# relays1.net
KiCad netlist of a schematic drawn in Altium Designer
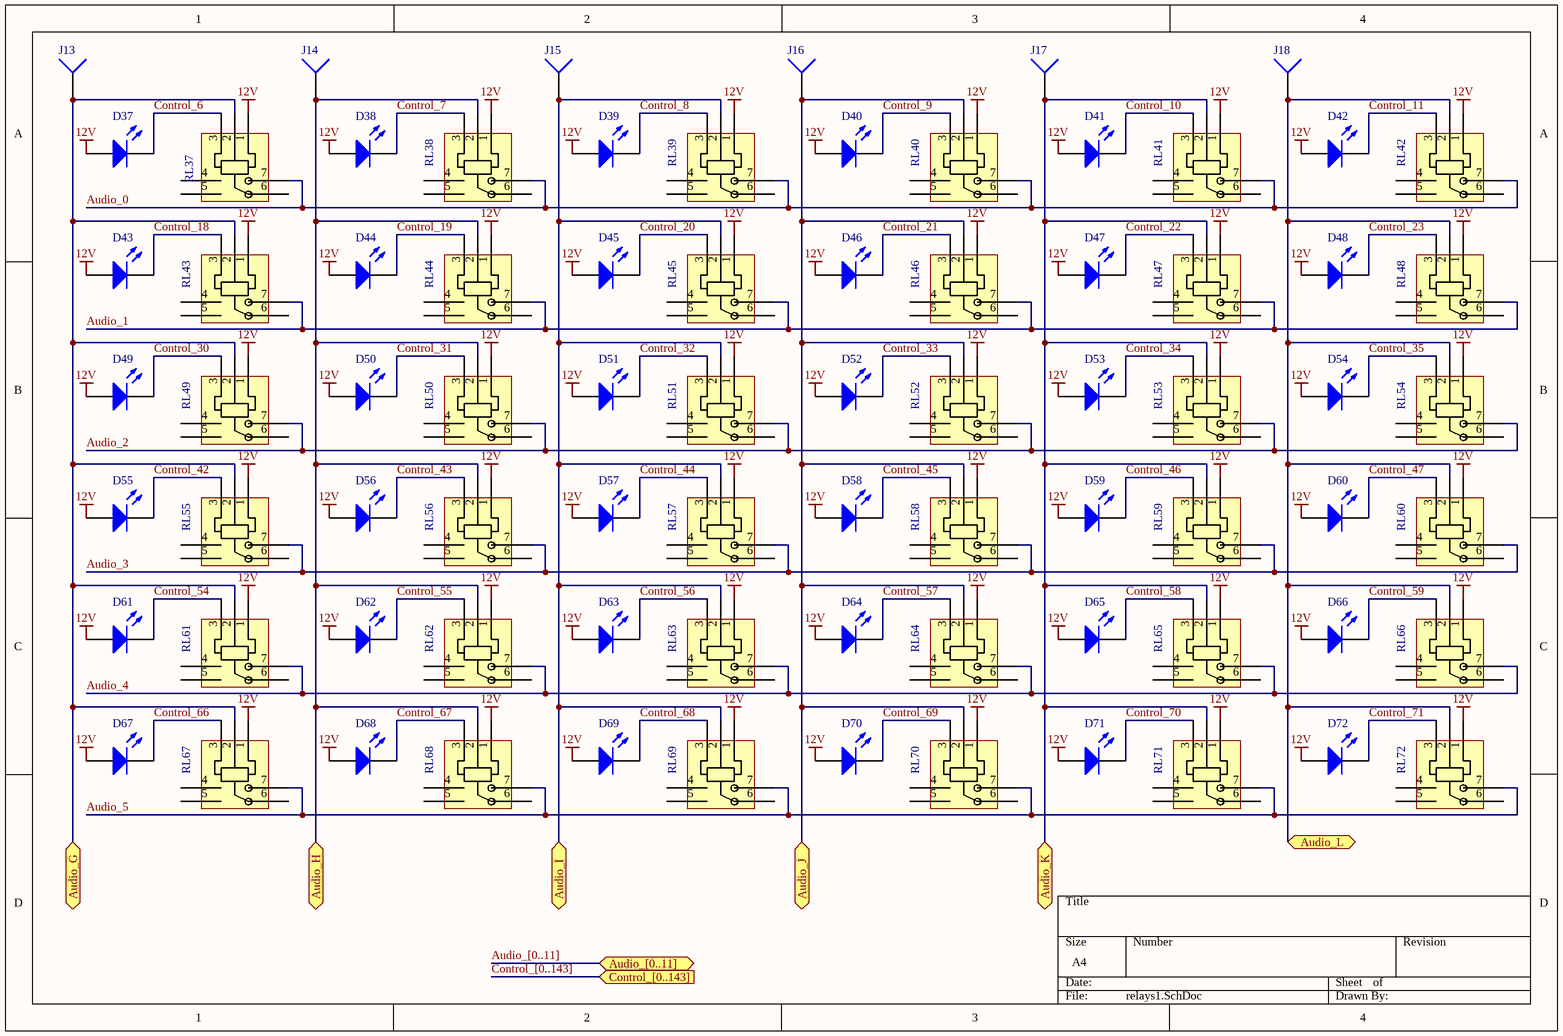
[diagram p0: relays1.SchDoc]

(export (version "E")
  (design (tool "Eeschema 10.0.6"))
  (components
    (comp (ref "D37")
      (value "LED0")
      (footprint "LED_round_5mm")
      (description "Typical INFRARED GaAs LED")
      (fields (field (name "PUBLISHER") "Altium Limited"))
      (libsource (lib "Miscellaneous Devices") (part "LED0"))
    )
    (comp (ref "D38")
      (value "LED0")
      (footprint "LED_round_5mm")
      (description "Typical INFRARED GaAs LED")
      (fields (field (name "PUBLISHER") "Altium Limited"))
      (libsource (lib "Miscellaneous Devices") (part "LED0"))
    )
    (comp (ref "D39")
      (value "LED0")
      (footprint "LED_round_5mm")
      (description "Typical INFRARED GaAs LED")
      (fields (field (name "PUBLISHER") "Altium Limited"))
      (libsource (lib "Miscellaneous Devices") (part "LED0"))
    )
    (comp (ref "D40")
      (value "LED0")
      (footprint "LED_round_5mm")
      (description "Typical INFRARED GaAs LED")
      (fields (field (name "PUBLISHER") "Altium Limited"))
      (libsource (lib "Miscellaneous Devices") (part "LED0"))
    )
    (comp (ref "D41")
      (value "LED0")
      (footprint "LED_round_5mm")
      (description "Typical INFRARED GaAs LED")
      (fields (field (name "PUBLISHER") "Altium Limited"))
      (libsource (lib "Miscellaneous Devices") (part "LED0"))
    )
    (comp (ref "D42")
      (value "LED0")
      (footprint "LED_round_5mm")
      (description "Typical INFRARED GaAs LED")
      (fields (field (name "PUBLISHER") "Altium Limited"))
      (libsource (lib "Miscellaneous Devices") (part "LED0"))
    )
    (comp (ref "D43")
      (value "LED0")
      (footprint "LED_round_5mm")
      (description "Typical INFRARED GaAs LED")
      (fields (field (name "PUBLISHER") "Altium Limited"))
      (libsource (lib "Miscellaneous Devices") (part "LED0"))
    )
    (comp (ref "D44")
      (value "LED0")
      (footprint "LED_round_5mm")
      (description "Typical INFRARED GaAs LED")
      (fields (field (name "PUBLISHER") "Altium Limited"))
      (libsource (lib "Miscellaneous Devices") (part "LED0"))
    )
    (comp (ref "D45")
      (value "LED0")
      (footprint "LED_round_5mm")
      (description "Typical INFRARED GaAs LED")
      (fields (field (name "PUBLISHER") "Altium Limited"))
      (libsource (lib "Miscellaneous Devices") (part "LED0"))
    )
    (comp (ref "D46")
      (value "LED0")
      (footprint "LED_round_5mm")
      (description "Typical INFRARED GaAs LED")
      (fields (field (name "PUBLISHER") "Altium Limited"))
      (libsource (lib "Miscellaneous Devices") (part "LED0"))
    )
    (comp (ref "D47")
      (value "LED0")
      (footprint "LED_round_5mm")
      (description "Typical INFRARED GaAs LED")
      (fields (field (name "PUBLISHER") "Altium Limited"))
      (libsource (lib "Miscellaneous Devices") (part "LED0"))
    )
    (comp (ref "D48")
      (value "LED0")
      (footprint "LED_round_5mm")
      (description "Typical INFRARED GaAs LED")
      (fields (field (name "PUBLISHER") "Altium Limited"))
      (libsource (lib "Miscellaneous Devices") (part "LED0"))
    )
    (comp (ref "D49")
      (value "LED0")
      (footprint "LED_round_5mm")
      (description "Typical INFRARED GaAs LED")
      (fields (field (name "PUBLISHER") "Altium Limited"))
      (libsource (lib "Miscellaneous Devices") (part "LED0"))
    )
    (comp (ref "D50")
      (value "LED0")
      (footprint "LED_round_5mm")
      (description "Typical INFRARED GaAs LED")
      (fields (field (name "PUBLISHER") "Altium Limited"))
      (libsource (lib "Miscellaneous Devices") (part "LED0"))
    )
    (comp (ref "D51")
      (value "LED0")
      (footprint "LED_round_5mm")
      (description "Typical INFRARED GaAs LED")
      (fields (field (name "PUBLISHER") "Altium Limited"))
      (libsource (lib "Miscellaneous Devices") (part "LED0"))
    )
    (comp (ref "D52")
      (value "LED0")
      (footprint "LED_round_5mm")
      (description "Typical INFRARED GaAs LED")
      (fields (field (name "PUBLISHER") "Altium Limited"))
      (libsource (lib "Miscellaneous Devices") (part "LED0"))
    )
    (comp (ref "D53")
      (value "LED0")
      (footprint "LED_round_5mm")
      (description "Typical INFRARED GaAs LED")
      (fields (field (name "PUBLISHER") "Altium Limited"))
      (libsource (lib "Miscellaneous Devices") (part "LED0"))
    )
    (comp (ref "D54")
      (value "LED0")
      (footprint "LED_round_5mm")
      (description "Typical INFRARED GaAs LED")
      (fields (field (name "PUBLISHER") "Altium Limited"))
      (libsource (lib "Miscellaneous Devices") (part "LED0"))
    )
    (comp (ref "D55")
      (value "LED0")
      (footprint "LED_round_5mm")
      (description "Typical INFRARED GaAs LED")
      (fields (field (name "PUBLISHER") "Altium Limited"))
      (libsource (lib "Miscellaneous Devices") (part "LED0"))
    )
    (comp (ref "D56")
      (value "LED0")
      (footprint "LED_round_5mm")
      (description "Typical INFRARED GaAs LED")
      (fields (field (name "PUBLISHER") "Altium Limited"))
      (libsource (lib "Miscellaneous Devices") (part "LED0"))
    )
    (comp (ref "D57")
      (value "LED0")
      (footprint "LED_round_5mm")
      (description "Typical INFRARED GaAs LED")
      (fields (field (name "PUBLISHER") "Altium Limited"))
      (libsource (lib "Miscellaneous Devices") (part "LED0"))
    )
    (comp (ref "D58")
      (value "LED0")
      (footprint "LED_round_5mm")
      (description "Typical INFRARED GaAs LED")
      (fields (field (name "PUBLISHER") "Altium Limited"))
      (libsource (lib "Miscellaneous Devices") (part "LED0"))
    )
    (comp (ref "D59")
      (value "LED0")
      (footprint "LED_round_5mm")
      (description "Typical INFRARED GaAs LED")
      (fields (field (name "PUBLISHER") "Altium Limited"))
      (libsource (lib "Miscellaneous Devices") (part "LED0"))
    )
    (comp (ref "D60")
      (value "LED0")
      (footprint "LED_round_5mm")
      (description "Typical INFRARED GaAs LED")
      (fields (field (name "PUBLISHER") "Altium Limited"))
      (libsource (lib "Miscellaneous Devices") (part "LED0"))
    )
    (comp (ref "D61")
      (value "LED0")
      (footprint "LED_round_5mm")
      (description "Typical INFRARED GaAs LED")
      (fields (field (name "PUBLISHER") "Altium Limited"))
      (libsource (lib "Miscellaneous Devices") (part "LED0"))
    )
    (comp (ref "D62")
      (value "LED0")
      (footprint "LED_round_5mm")
      (description "Typical INFRARED GaAs LED")
      (fields (field (name "PUBLISHER") "Altium Limited"))
      (libsource (lib "Miscellaneous Devices") (part "LED0"))
    )
    (comp (ref "D63")
      (value "LED0")
      (footprint "LED_round_5mm")
      (description "Typical INFRARED GaAs LED")
      (fields (field (name "PUBLISHER") "Altium Limited"))
      (libsource (lib "Miscellaneous Devices") (part "LED0"))
    )
    (comp (ref "D64")
      (value "LED0")
      (footprint "LED_round_5mm")
      (description "Typical INFRARED GaAs LED")
      (fields (field (name "PUBLISHER") "Altium Limited"))
      (libsource (lib "Miscellaneous Devices") (part "LED0"))
    )
    (comp (ref "D65")
      (value "LED0")
      (footprint "LED_round_5mm")
      (description "Typical INFRARED GaAs LED")
      (fields (field (name "PUBLISHER") "Altium Limited"))
      (libsource (lib "Miscellaneous Devices") (part "LED0"))
    )
    (comp (ref "D66")
      (value "LED0")
      (footprint "LED_round_5mm")
      (description "Typical INFRARED GaAs LED")
      (fields (field (name "PUBLISHER") "Altium Limited"))
      (libsource (lib "Miscellaneous Devices") (part "LED0"))
    )
    (comp (ref "D67")
      (value "LED0")
      (footprint "LED_round_5mm")
      (description "Typical INFRARED GaAs LED")
      (fields (field (name "PUBLISHER") "Altium Limited"))
      (libsource (lib "Miscellaneous Devices") (part "LED0"))
    )
    (comp (ref "D68")
      (value "LED0")
      (footprint "LED_round_5mm")
      (description "Typical INFRARED GaAs LED")
      (fields (field (name "PUBLISHER") "Altium Limited"))
      (libsource (lib "Miscellaneous Devices") (part "LED0"))
    )
    (comp (ref "D69")
      (value "LED0")
      (footprint "LED_round_5mm")
      (description "Typical INFRARED GaAs LED")
      (fields (field (name "PUBLISHER") "Altium Limited"))
      (libsource (lib "Miscellaneous Devices") (part "LED0"))
    )
    (comp (ref "D70")
      (value "LED0")
      (footprint "LED_round_5mm")
      (description "Typical INFRARED GaAs LED")
      (fields (field (name "PUBLISHER") "Altium Limited"))
      (libsource (lib "Miscellaneous Devices") (part "LED0"))
    )
    (comp (ref "D71")
      (value "LED0")
      (footprint "LED_round_5mm")
      (description "Typical INFRARED GaAs LED")
      (fields (field (name "PUBLISHER") "Altium Limited"))
      (libsource (lib "Miscellaneous Devices") (part "LED0"))
    )
    (comp (ref "D72")
      (value "LED0")
      (footprint "LED_round_5mm")
      (description "Typical INFRARED GaAs LED")
      (fields (field (name "PUBLISHER") "Altium Limited"))
      (libsource (lib "Miscellaneous Devices") (part "LED0"))
    )
    (comp (ref "J13")
      (value "Audio")
      (footprint "Conn_1_2x4")
      (description "Socket")
      (fields (field (name "PUBLISHER") "Altium Limited"))
      (libsource (lib "Miscellaneous Connectors") (part "Socket"))
    )
    (comp (ref "J14")
      (value "Audio")
      (footprint "Conn_1_2x4")
      (description "Socket")
      (fields (field (name "PUBLISHER") "Altium Limited"))
      (libsource (lib "Miscellaneous Connectors") (part "Socket"))
    )
    (comp (ref "J15")
      (value "Audio")
      (footprint "Conn_1_2x4")
      (description "Socket")
      (fields (field (name "PUBLISHER") "Altium Limited"))
      (libsource (lib "Miscellaneous Connectors") (part "Socket"))
    )
    (comp (ref "J16")
      (value "Audio")
      (footprint "Conn_1_2x4")
      (description "Socket")
      (fields (field (name "PUBLISHER") "Altium Limited"))
      (libsource (lib "Miscellaneous Connectors") (part "Socket"))
    )
    (comp (ref "J17")
      (value "Audio")
      (footprint "Conn_1_2x4")
      (description "Socket")
      (fields (field (name "PUBLISHER") "Altium Limited"))
      (libsource (lib "Miscellaneous Connectors") (part "Socket"))
    )
    (comp (ref "J18")
      (value "Audio")
      (footprint "Conn_1_2x4")
      (description "Socket")
      (fields (field (name "PUBLISHER") "Altium Limited"))
      (libsource (lib "Miscellaneous Connectors") (part "Socket"))
    )
    (comp (ref "RL37")
      (value "Relay")
      (footprint "Relay_FRA3")
      (description "Miniature power relay")
      (fields (field (name "PART NUMBER") "FRA3C-DC12"))
      (libsource (lib "tech-thing") (part "Relay_FRA3"))
    )
    (comp (ref "RL38")
      (value "Relay")
      (footprint "Relay_FRA3")
      (description "Miniature power relay")
      (fields (field (name "PART NUMBER") "FRA3C-DC12"))
      (libsource (lib "tech-thing") (part "Relay_FRA3"))
    )
    (comp (ref "RL39")
      (value "Relay")
      (footprint "Relay_FRA3")
      (description "Miniature power relay")
      (fields (field (name "PART NUMBER") "FRA3C-DC12"))
      (libsource (lib "tech-thing") (part "Relay_FRA3"))
    )
    (comp (ref "RL40")
      (value "Relay")
      (footprint "Relay_FRA3")
      (description "Miniature power relay")
      (fields (field (name "PART NUMBER") "FRA3C-DC12"))
      (libsource (lib "tech-thing") (part "Relay_FRA3"))
    )
    (comp (ref "RL41")
      (value "Relay")
      (footprint "Relay_FRA3")
      (description "Miniature power relay")
      (fields (field (name "PART NUMBER") "FRA3C-DC12"))
      (libsource (lib "tech-thing") (part "Relay_FRA3"))
    )
    (comp (ref "RL42")
      (value "Relay")
      (footprint "Relay_FRA3")
      (description "Miniature power relay")
      (fields (field (name "PART NUMBER") "FRA3C-DC12"))
      (libsource (lib "tech-thing") (part "Relay_FRA3"))
    )
    (comp (ref "RL43")
      (value "Relay")
      (footprint "Relay_FRA3")
      (description "Miniature power relay")
      (fields (field (name "PART NUMBER") "FRA3C-DC12"))
      (libsource (lib "tech-thing") (part "Relay_FRA3"))
    )
    (comp (ref "RL44")
      (value "Relay")
      (footprint "Relay_FRA3")
      (description "Miniature power relay")
      (fields (field (name "PART NUMBER") "FRA3C-DC12"))
      (libsource (lib "tech-thing") (part "Relay_FRA3"))
    )
    (comp (ref "RL45")
      (value "Relay")
      (footprint "Relay_FRA3")
      (description "Miniature power relay")
      (fields (field (name "PART NUMBER") "FRA3C-DC12"))
      (libsource (lib "tech-thing") (part "Relay_FRA3"))
    )
    (comp (ref "RL46")
      (value "Relay")
      (footprint "Relay_FRA3")
      (description "Miniature power relay")
      (fields (field (name "PART NUMBER") "FRA3C-DC12"))
      (libsource (lib "tech-thing") (part "Relay_FRA3"))
    )
    (comp (ref "RL47")
      (value "Relay")
      (footprint "Relay_FRA3")
      (description "Miniature power relay")
      (fields (field (name "PART NUMBER") "FRA3C-DC12"))
      (libsource (lib "tech-thing") (part "Relay_FRA3"))
    )
    (comp (ref "RL48")
      (value "Relay")
      (footprint "Relay_FRA3")
      (description "Miniature power relay")
      (fields (field (name "PART NUMBER") "FRA3C-DC12"))
      (libsource (lib "tech-thing") (part "Relay_FRA3"))
    )
    (comp (ref "RL49")
      (value "Relay")
      (footprint "Relay_FRA3")
      (description "Miniature power relay")
      (fields (field (name "PART NUMBER") "FRA3C-DC12"))
      (libsource (lib "tech-thing") (part "Relay_FRA3"))
    )
    (comp (ref "RL50")
      (value "Relay")
      (footprint "Relay_FRA3")
      (description "Miniature power relay")
      (fields (field (name "PART NUMBER") "FRA3C-DC12"))
      (libsource (lib "tech-thing") (part "Relay_FRA3"))
    )
    (comp (ref "RL51")
      (value "Relay")
      (footprint "Relay_FRA3")
      (description "Miniature power relay")
      (fields (field (name "PART NUMBER") "FRA3C-DC12"))
      (libsource (lib "tech-thing") (part "Relay_FRA3"))
    )
    (comp (ref "RL52")
      (value "Relay")
      (footprint "Relay_FRA3")
      (description "Miniature power relay")
      (fields (field (name "PART NUMBER") "FRA3C-DC12"))
      (libsource (lib "tech-thing") (part "Relay_FRA3"))
    )
    (comp (ref "RL53")
      (value "Relay")
      (footprint "Relay_FRA3")
      (description "Miniature power relay")
      (fields (field (name "PART NUMBER") "FRA3C-DC12"))
      (libsource (lib "tech-thing") (part "Relay_FRA3"))
    )
    (comp (ref "RL54")
      (value "Relay")
      (footprint "Relay_FRA3")
      (description "Miniature power relay")
      (fields (field (name "PART NUMBER") "FRA3C-DC12"))
      (libsource (lib "tech-thing") (part "Relay_FRA3"))
    )
    (comp (ref "RL55")
      (value "Relay")
      (footprint "Relay_FRA3")
      (description "Miniature power relay")
      (fields (field (name "PART NUMBER") "FRA3C-DC12"))
      (libsource (lib "tech-thing") (part "Relay_FRA3"))
    )
    (comp (ref "RL56")
      (value "Relay")
      (footprint "Relay_FRA3")
      (description "Miniature power relay")
      (fields (field (name "PART NUMBER") "FRA3C-DC12"))
      (libsource (lib "tech-thing") (part "Relay_FRA3"))
    )
    (comp (ref "RL57")
      (value "Relay")
      (footprint "Relay_FRA3")
      (description "Miniature power relay")
      (fields (field (name "PART NUMBER") "FRA3C-DC12"))
      (libsource (lib "tech-thing") (part "Relay_FRA3"))
    )
    (comp (ref "RL58")
      (value "Relay")
      (footprint "Relay_FRA3")
      (description "Miniature power relay")
      (fields (field (name "PART NUMBER") "FRA3C-DC12"))
      (libsource (lib "tech-thing") (part "Relay_FRA3"))
    )
    (comp (ref "RL59")
      (value "Relay")
      (footprint "Relay_FRA3")
      (description "Miniature power relay")
      (fields (field (name "PART NUMBER") "FRA3C-DC12"))
      (libsource (lib "tech-thing") (part "Relay_FRA3"))
    )
    (comp (ref "RL60")
      (value "Relay")
      (footprint "Relay_FRA3")
      (description "Miniature power relay")
      (fields (field (name "PART NUMBER") "FRA3C-DC12"))
      (libsource (lib "tech-thing") (part "Relay_FRA3"))
    )
    (comp (ref "RL61")
      (value "Relay")
      (footprint "Relay_FRA3")
      (description "Miniature power relay")
      (fields (field (name "PART NUMBER") "FRA3C-DC12"))
      (libsource (lib "tech-thing") (part "Relay_FRA3"))
    )
    (comp (ref "RL62")
      (value "Relay")
      (footprint "Relay_FRA3")
      (description "Miniature power relay")
      (fields (field (name "PART NUMBER") "FRA3C-DC12"))
      (libsource (lib "tech-thing") (part "Relay_FRA3"))
    )
    (comp (ref "RL63")
      (value "Relay")
      (footprint "Relay_FRA3")
      (description "Miniature power relay")
      (fields (field (name "PART NUMBER") "FRA3C-DC12"))
      (libsource (lib "tech-thing") (part "Relay_FRA3"))
    )
    (comp (ref "RL64")
      (value "Relay")
      (footprint "Relay_FRA3")
      (description "Miniature power relay")
      (fields (field (name "PART NUMBER") "FRA3C-DC12"))
      (libsource (lib "tech-thing") (part "Relay_FRA3"))
    )
    (comp (ref "RL65")
      (value "Relay")
      (footprint "Relay_FRA3")
      (description "Miniature power relay")
      (fields (field (name "PART NUMBER") "FRA3C-DC12"))
      (libsource (lib "tech-thing") (part "Relay_FRA3"))
    )
    (comp (ref "RL66")
      (value "Relay")
      (footprint "Relay_FRA3")
      (description "Miniature power relay")
      (fields (field (name "PART NUMBER") "FRA3C-DC12"))
      (libsource (lib "tech-thing") (part "Relay_FRA3"))
    )
    (comp (ref "RL67")
      (value "Relay")
      (footprint "Relay_FRA3")
      (description "Miniature power relay")
      (fields (field (name "PART NUMBER") "FRA3C-DC12"))
      (libsource (lib "tech-thing") (part "Relay_FRA3"))
    )
    (comp (ref "RL68")
      (value "Relay")
      (footprint "Relay_FRA3")
      (description "Miniature power relay")
      (fields (field (name "PART NUMBER") "FRA3C-DC12"))
      (libsource (lib "tech-thing") (part "Relay_FRA3"))
    )
    (comp (ref "RL69")
      (value "Relay")
      (footprint "Relay_FRA3")
      (description "Miniature power relay")
      (fields (field (name "PART NUMBER") "FRA3C-DC12"))
      (libsource (lib "tech-thing") (part "Relay_FRA3"))
    )
    (comp (ref "RL70")
      (value "Relay")
      (footprint "Relay_FRA3")
      (description "Miniature power relay")
      (fields (field (name "PART NUMBER") "FRA3C-DC12"))
      (libsource (lib "tech-thing") (part "Relay_FRA3"))
    )
    (comp (ref "RL71")
      (value "Relay")
      (footprint "Relay_FRA3")
      (description "Miniature power relay")
      (fields (field (name "PART NUMBER") "FRA3C-DC12"))
      (libsource (lib "tech-thing") (part "Relay_FRA3"))
    )
    (comp (ref "RL72")
      (value "Relay")
      (footprint "Relay_FRA3")
      (description "Miniature power relay")
      (fields (field (name "PART NUMBER") "FRA3C-DC12"))
      (libsource (lib "tech-thing") (part "Relay_FRA3"))
    )
  )
  (nets
    (net (code "115") (name "/Audio_0") (class "Default")
      (node (ref "RL37") (pin "7") (pintype "passive"))
      (node (ref "RL38") (pin "7") (pintype "passive"))
      (node (ref "RL39") (pin "7") (pintype "passive"))
      (node (ref "RL40") (pin "7") (pintype "passive"))
      (node (ref "RL41") (pin "7") (pintype "passive"))
      (node (ref "RL42") (pin "7") (pintype "passive"))
    )
    (net (code "116") (name "/Audio_1") (class "Default")
      (node (ref "RL43") (pin "7") (pintype "passive"))
      (node (ref "RL44") (pin "7") (pintype "passive"))
      (node (ref "RL45") (pin "7") (pintype "passive"))
      (node (ref "RL46") (pin "7") (pintype "passive"))
      (node (ref "RL47") (pin "7") (pintype "passive"))
      (node (ref "RL48") (pin "7") (pintype "passive"))
    )
    (net (code "117") (name "/Audio_2") (class "Default")
      (node (ref "RL49") (pin "7") (pintype "passive"))
      (node (ref "RL50") (pin "7") (pintype "passive"))
      (node (ref "RL51") (pin "7") (pintype "passive"))
      (node (ref "RL52") (pin "7") (pintype "passive"))
      (node (ref "RL53") (pin "7") (pintype "passive"))
      (node (ref "RL54") (pin "7") (pintype "passive"))
    )
    (net (code "118") (name "/Audio_3") (class "Default")
      (node (ref "RL55") (pin "7") (pintype "passive"))
      (node (ref "RL56") (pin "7") (pintype "passive"))
      (node (ref "RL57") (pin "7") (pintype "passive"))
      (node (ref "RL58") (pin "7") (pintype "passive"))
      (node (ref "RL59") (pin "7") (pintype "passive"))
      (node (ref "RL60") (pin "7") (pintype "passive"))
    )
    (net (code "119") (name "/Audio_4") (class "Default")
      (node (ref "RL61") (pin "7") (pintype "passive"))
      (node (ref "RL62") (pin "7") (pintype "passive"))
      (node (ref "RL63") (pin "7") (pintype "passive"))
      (node (ref "RL64") (pin "7") (pintype "passive"))
      (node (ref "RL65") (pin "7") (pintype "passive"))
      (node (ref "RL66") (pin "7") (pintype "passive"))
    )
    (net (code "120") (name "/Audio_5") (class "Default")
      (node (ref "RL67") (pin "7") (pintype "passive"))
      (node (ref "RL68") (pin "7") (pintype "passive"))
      (node (ref "RL69") (pin "7") (pintype "passive"))
      (node (ref "RL70") (pin "7") (pintype "passive"))
      (node (ref "RL71") (pin "7") (pintype "passive"))
      (node (ref "RL72") (pin "7") (pintype "passive"))
    )
    (net (code "121") (name "/Audio_G") (class "Default")
      (node (ref "J13") (pin "1") (pinfunction "1_1") (pintype "passive"))
      (node (ref "RL37") (pin "2") (pintype "passive"))
      (node (ref "RL43") (pin "2") (pintype "passive"))
      (node (ref "RL49") (pin "2") (pintype "passive"))
      (node (ref "RL55") (pin "2") (pintype "passive"))
      (node (ref "RL61") (pin "2") (pintype "passive"))
      (node (ref "RL67") (pin "2") (pintype "passive"))
    )
    (net (code "122") (name "/Audio_H") (class "Default")
      (node (ref "J14") (pin "1") (pinfunction "1_1") (pintype "passive"))
      (node (ref "RL38") (pin "2") (pintype "passive"))
      (node (ref "RL44") (pin "2") (pintype "passive"))
      (node (ref "RL50") (pin "2") (pintype "passive"))
      (node (ref "RL56") (pin "2") (pintype "passive"))
      (node (ref "RL62") (pin "2") (pintype "passive"))
      (node (ref "RL68") (pin "2") (pintype "passive"))
    )
    (net (code "123") (name "/Audio_I") (class "Default")
      (node (ref "J15") (pin "1") (pinfunction "1_1") (pintype "passive"))
      (node (ref "RL39") (pin "2") (pintype "passive"))
      (node (ref "RL45") (pin "2") (pintype "passive"))
      (node (ref "RL51") (pin "2") (pintype "passive"))
      (node (ref "RL57") (pin "2") (pintype "passive"))
      (node (ref "RL63") (pin "2") (pintype "passive"))
      (node (ref "RL69") (pin "2") (pintype "passive"))
    )
    (net (code "124") (name "/Audio_J") (class "Default")
      (node (ref "J16") (pin "1") (pinfunction "1_1") (pintype "passive"))
      (node (ref "RL40") (pin "2") (pintype "passive"))
      (node (ref "RL46") (pin "2") (pintype "passive"))
      (node (ref "RL52") (pin "2") (pintype "passive"))
      (node (ref "RL58") (pin "2") (pintype "passive"))
      (node (ref "RL64") (pin "2") (pintype "passive"))
      (node (ref "RL70") (pin "2") (pintype "passive"))
    )
    (net (code "125") (name "/Audio_K") (class "Default")
      (node (ref "J17") (pin "1") (pinfunction "1_1") (pintype "passive"))
      (node (ref "RL41") (pin "2") (pintype "passive"))
      (node (ref "RL47") (pin "2") (pintype "passive"))
      (node (ref "RL53") (pin "2") (pintype "passive"))
      (node (ref "RL59") (pin "2") (pintype "passive"))
      (node (ref "RL65") (pin "2") (pintype "passive"))
      (node (ref "RL71") (pin "2") (pintype "passive"))
    )
    (net (code "126") (name "/Audio_L") (class "Default")
      (node (ref "J18") (pin "1") (pinfunction "1_1") (pintype "passive"))
      (node (ref "RL42") (pin "2") (pintype "passive"))
      (node (ref "RL48") (pin "2") (pintype "passive"))
      (node (ref "RL54") (pin "2") (pintype "passive"))
      (node (ref "RL60") (pin "2") (pintype "passive"))
      (node (ref "RL66") (pin "2") (pintype "passive"))
      (node (ref "RL72") (pin "2") (pintype "passive"))
    )
    (net (code "128") (name "/Control_6") (class "Default")
      (node (ref "D37") (pin "2") (pinfunction "K_2") (pintype "passive"))
      (node (ref "RL37") (pin "3") (pintype "passive"))
    )
    (net (code "129") (name "/Control_7") (class "Default")
      (node (ref "D38") (pin "2") (pinfunction "K_2") (pintype "passive"))
      (node (ref "RL38") (pin "3") (pintype "passive"))
    )
    (net (code "130") (name "/Control_8") (class "Default")
      (node (ref "D39") (pin "2") (pinfunction "K_2") (pintype "passive"))
      (node (ref "RL39") (pin "3") (pintype "passive"))
    )
    (net (code "131") (name "/Control_9") (class "Default")
      (node (ref "D40") (pin "2") (pinfunction "K_2") (pintype "passive"))
      (node (ref "RL40") (pin "3") (pintype "passive"))
    )
    (net (code "132") (name "/Control_10") (class "Default")
      (node (ref "D41") (pin "2") (pinfunction "K_2") (pintype "passive"))
      (node (ref "RL41") (pin "3") (pintype "passive"))
    )
    (net (code "133") (name "/Control_11") (class "Default")
      (node (ref "D42") (pin "2") (pinfunction "K_2") (pintype "passive"))
      (node (ref "RL42") (pin "3") (pintype "passive"))
    )
    (net (code "134") (name "/Control_18") (class "Default")
      (node (ref "D43") (pin "2") (pinfunction "K_2") (pintype "passive"))
      (node (ref "RL43") (pin "3") (pintype "passive"))
    )
    (net (code "135") (name "/Control_19") (class "Default")
      (node (ref "D44") (pin "2") (pinfunction "K_2") (pintype "passive"))
      (node (ref "RL44") (pin "3") (pintype "passive"))
    )
    (net (code "136") (name "/Control_20") (class "Default")
      (node (ref "D45") (pin "2") (pinfunction "K_2") (pintype "passive"))
      (node (ref "RL45") (pin "3") (pintype "passive"))
    )
    (net (code "137") (name "/Control_21") (class "Default")
      (node (ref "D46") (pin "2") (pinfunction "K_2") (pintype "passive"))
      (node (ref "RL46") (pin "3") (pintype "passive"))
    )
    (net (code "138") (name "/Control_22") (class "Default")
      (node (ref "D47") (pin "2") (pinfunction "K_2") (pintype "passive"))
      (node (ref "RL47") (pin "3") (pintype "passive"))
    )
    (net (code "139") (name "/Control_23") (class "Default")
      (node (ref "D48") (pin "2") (pinfunction "K_2") (pintype "passive"))
      (node (ref "RL48") (pin "3") (pintype "passive"))
    )
    (net (code "140") (name "/Control_30") (class "Default")
      (node (ref "D49") (pin "2") (pinfunction "K_2") (pintype "passive"))
      (node (ref "RL49") (pin "3") (pintype "passive"))
    )
    (net (code "141") (name "/Control_31") (class "Default")
      (node (ref "D50") (pin "2") (pinfunction "K_2") (pintype "passive"))
      (node (ref "RL50") (pin "3") (pintype "passive"))
    )
    (net (code "142") (name "/Control_32") (class "Default")
      (node (ref "D51") (pin "2") (pinfunction "K_2") (pintype "passive"))
      (node (ref "RL51") (pin "3") (pintype "passive"))
    )
    (net (code "143") (name "/Control_33") (class "Default")
      (node (ref "D52") (pin "2") (pinfunction "K_2") (pintype "passive"))
      (node (ref "RL52") (pin "3") (pintype "passive"))
    )
    (net (code "144") (name "/Control_34") (class "Default")
      (node (ref "D53") (pin "2") (pinfunction "K_2") (pintype "passive"))
      (node (ref "RL53") (pin "3") (pintype "passive"))
    )
    (net (code "145") (name "/Control_35") (class "Default")
      (node (ref "D54") (pin "2") (pinfunction "K_2") (pintype "passive"))
      (node (ref "RL54") (pin "3") (pintype "passive"))
    )
    (net (code "146") (name "/Control_42") (class "Default")
      (node (ref "D55") (pin "2") (pinfunction "K_2") (pintype "passive"))
      (node (ref "RL55") (pin "3") (pintype "passive"))
    )
    (net (code "147") (name "/Control_43") (class "Default")
      (node (ref "D56") (pin "2") (pinfunction "K_2") (pintype "passive"))
      (node (ref "RL56") (pin "3") (pintype "passive"))
    )
    (net (code "148") (name "/Control_44") (class "Default")
      (node (ref "D57") (pin "2") (pinfunction "K_2") (pintype "passive"))
      (node (ref "RL57") (pin "3") (pintype "passive"))
    )
    (net (code "149") (name "/Control_45") (class "Default")
      (node (ref "D58") (pin "2") (pinfunction "K_2") (pintype "passive"))
      (node (ref "RL58") (pin "3") (pintype "passive"))
    )
    (net (code "150") (name "/Control_46") (class "Default")
      (node (ref "D59") (pin "2") (pinfunction "K_2") (pintype "passive"))
      (node (ref "RL59") (pin "3") (pintype "passive"))
    )
    (net (code "151") (name "/Control_47") (class "Default")
      (node (ref "D60") (pin "2") (pinfunction "K_2") (pintype "passive"))
      (node (ref "RL60") (pin "3") (pintype "passive"))
    )
    (net (code "152") (name "/Control_54") (class "Default")
      (node (ref "D61") (pin "2") (pinfunction "K_2") (pintype "passive"))
      (node (ref "RL61") (pin "3") (pintype "passive"))
    )
    (net (code "153") (name "/Control_55") (class "Default")
      (node (ref "D62") (pin "2") (pinfunction "K_2") (pintype "passive"))
      (node (ref "RL62") (pin "3") (pintype "passive"))
    )
    (net (code "154") (name "/Control_56") (class "Default")
      (node (ref "D63") (pin "2") (pinfunction "K_2") (pintype "passive"))
      (node (ref "RL63") (pin "3") (pintype "passive"))
    )
    (net (code "155") (name "/Control_57") (class "Default")
      (node (ref "D64") (pin "2") (pinfunction "K_2") (pintype "passive"))
      (node (ref "RL64") (pin "3") (pintype "passive"))
    )
    (net (code "156") (name "/Control_58") (class "Default")
      (node (ref "D65") (pin "2") (pinfunction "K_2") (pintype "passive"))
      (node (ref "RL65") (pin "3") (pintype "passive"))
    )
    (net (code "157") (name "/Control_59") (class "Default")
      (node (ref "D66") (pin "2") (pinfunction "K_2") (pintype "passive"))
      (node (ref "RL66") (pin "3") (pintype "passive"))
    )
    (net (code "158") (name "/Control_66") (class "Default")
      (node (ref "D67") (pin "2") (pinfunction "K_2") (pintype "passive"))
      (node (ref "RL67") (pin "3") (pintype "passive"))
    )
    (net (code "159") (name "/Control_67") (class "Default")
      (node (ref "D68") (pin "2") (pinfunction "K_2") (pintype "passive"))
      (node (ref "RL68") (pin "3") (pintype "passive"))
    )
    (net (code "160") (name "/Control_68") (class "Default")
      (node (ref "D69") (pin "2") (pinfunction "K_2") (pintype "passive"))
      (node (ref "RL69") (pin "3") (pintype "passive"))
    )
    (net (code "161") (name "/Control_69") (class "Default")
      (node (ref "D70") (pin "2") (pinfunction "K_2") (pintype "passive"))
      (node (ref "RL70") (pin "3") (pintype "passive"))
    )
    (net (code "162") (name "/Control_70") (class "Default")
      (node (ref "D71") (pin "2") (pinfunction "K_2") (pintype "passive"))
      (node (ref "RL71") (pin "3") (pintype "passive"))
    )
    (net (code "163") (name "/Control_71") (class "Default")
      (node (ref "D72") (pin "2") (pinfunction "K_2") (pintype "passive"))
      (node (ref "RL72") (pin "3") (pintype "passive"))
    )
    (net (code "165") (name "12V") (class "Default")
      (node (ref "D37") (pin "1") (pinfunction "A_1") (pintype "passive"))
      (node (ref "D38") (pin "1") (pinfunction "A_1") (pintype "passive"))
      (node (ref "D39") (pin "1") (pinfunction "A_1") (pintype "passive"))
      (node (ref "D40") (pin "1") (pinfunction "A_1") (pintype "passive"))
      (node (ref "D41") (pin "1") (pinfunction "A_1") (pintype "passive"))
      (node (ref "D42") (pin "1") (pinfunction "A_1") (pintype "passive"))
      (node (ref "D43") (pin "1") (pinfunction "A_1") (pintype "passive"))
      (node (ref "D44") (pin "1") (pinfunction "A_1") (pintype "passive"))
      (node (ref "D45") (pin "1") (pinfunction "A_1") (pintype "passive"))
      (node (ref "D46") (pin "1") (pinfunction "A_1") (pintype "passive"))
      (node (ref "D47") (pin "1") (pinfunction "A_1") (pintype "passive"))
      (node (ref "D48") (pin "1") (pinfunction "A_1") (pintype "passive"))
      (node (ref "D49") (pin "1") (pinfunction "A_1") (pintype "passive"))
      (node (ref "D50") (pin "1") (pinfunction "A_1") (pintype "passive"))
      (node (ref "D51") (pin "1") (pinfunction "A_1") (pintype "passive"))
      (node (ref "D52") (pin "1") (pinfunction "A_1") (pintype "passive"))
      (node (ref "D53") (pin "1") (pinfunction "A_1") (pintype "passive"))
      (node (ref "D54") (pin "1") (pinfunction "A_1") (pintype "passive"))
      (node (ref "D55") (pin "1") (pinfunction "A_1") (pintype "passive"))
      (node (ref "D56") (pin "1") (pinfunction "A_1") (pintype "passive"))
      (node (ref "D57") (pin "1") (pinfunction "A_1") (pintype "passive"))
      (node (ref "D58") (pin "1") (pinfunction "A_1") (pintype "passive"))
      (node (ref "D59") (pin "1") (pinfunction "A_1") (pintype "passive"))
      (node (ref "D60") (pin "1") (pinfunction "A_1") (pintype "passive"))
      (node (ref "D61") (pin "1") (pinfunction "A_1") (pintype "passive"))
      (node (ref "D62") (pin "1") (pinfunction "A_1") (pintype "passive"))
      (node (ref "D63") (pin "1") (pinfunction "A_1") (pintype "passive"))
      (node (ref "D64") (pin "1") (pinfunction "A_1") (pintype "passive"))
      (node (ref "D65") (pin "1") (pinfunction "A_1") (pintype "passive"))
      (node (ref "D66") (pin "1") (pinfunction "A_1") (pintype "passive"))
      (node (ref "D67") (pin "1") (pinfunction "A_1") (pintype "passive"))
      (node (ref "D68") (pin "1") (pinfunction "A_1") (pintype "passive"))
      (node (ref "D69") (pin "1") (pinfunction "A_1") (pintype "passive"))
      (node (ref "D70") (pin "1") (pinfunction "A_1") (pintype "passive"))
      (node (ref "D71") (pin "1") (pinfunction "A_1") (pintype "passive"))
      (node (ref "D72") (pin "1") (pinfunction "A_1") (pintype "passive"))
      (node (ref "RL37") (pin "1") (pintype "passive"))
      (node (ref "RL38") (pin "1") (pintype "passive"))
      (node (ref "RL39") (pin "1") (pintype "passive"))
      (node (ref "RL40") (pin "1") (pintype "passive"))
      (node (ref "RL41") (pin "1") (pintype "passive"))
      (node (ref "RL42") (pin "1") (pintype "passive"))
      (node (ref "RL43") (pin "1") (pintype "passive"))
      (node (ref "RL44") (pin "1") (pintype "passive"))
      (node (ref "RL45") (pin "1") (pintype "passive"))
      (node (ref "RL46") (pin "1") (pintype "passive"))
      (node (ref "RL47") (pin "1") (pintype "passive"))
      (node (ref "RL48") (pin "1") (pintype "passive"))
      (node (ref "RL49") (pin "1") (pintype "passive"))
      (node (ref "RL50") (pin "1") (pintype "passive"))
      (node (ref "RL51") (pin "1") (pintype "passive"))
      (node (ref "RL52") (pin "1") (pintype "passive"))
      (node (ref "RL53") (pin "1") (pintype "passive"))
      (node (ref "RL54") (pin "1") (pintype "passive"))
      (node (ref "RL55") (pin "1") (pintype "passive"))
      (node (ref "RL56") (pin "1") (pintype "passive"))
      (node (ref "RL57") (pin "1") (pintype "passive"))
      (node (ref "RL58") (pin "1") (pintype "passive"))
      (node (ref "RL59") (pin "1") (pintype "passive"))
      (node (ref "RL60") (pin "1") (pintype "passive"))
      (node (ref "RL61") (pin "1") (pintype "passive"))
      (node (ref "RL62") (pin "1") (pintype "passive"))
      (node (ref "RL63") (pin "1") (pintype "passive"))
      (node (ref "RL64") (pin "1") (pintype "passive"))
      (node (ref "RL65") (pin "1") (pintype "passive"))
      (node (ref "RL66") (pin "1") (pintype "passive"))
      (node (ref "RL67") (pin "1") (pintype "passive"))
      (node (ref "RL68") (pin "1") (pintype "passive"))
      (node (ref "RL69") (pin "1") (pintype "passive"))
      (node (ref "RL70") (pin "1") (pintype "passive"))
      (node (ref "RL71") (pin "1") (pintype "passive"))
      (node (ref "RL72") (pin "1") (pintype "passive"))
    )
    (net (code "166") (name "unconnected-(RL37-Pad4)") (class "Default")
      (node (ref "RL37") (pin "4") (pintype "passive"))
    )
    (net (code "167") (name "unconnected-(RL37-Pad5)") (class "Default")
      (node (ref "RL37") (pin "5") (pintype "passive"))
    )
    (net (code "168") (name "unconnected-(RL37-Pad6)") (class "Default")
      (node (ref "RL37") (pin "6") (pintype "passive"))
    )
    (net (code "169") (name "unconnected-(RL38-Pad4)") (class "Default")
      (node (ref "RL38") (pin "4") (pintype "passive"))
    )
    (net (code "170") (name "unconnected-(RL38-Pad5)") (class "Default")
      (node (ref "RL38") (pin "5") (pintype "passive"))
    )
    (net (code "171") (name "unconnected-(RL38-Pad6)") (class "Default")
      (node (ref "RL38") (pin "6") (pintype "passive"))
    )
    (net (code "172") (name "unconnected-(RL39-Pad4)") (class "Default")
      (node (ref "RL39") (pin "4") (pintype "passive"))
    )
    (net (code "173") (name "unconnected-(RL39-Pad5)") (class "Default")
      (node (ref "RL39") (pin "5") (pintype "passive"))
    )
    (net (code "174") (name "unconnected-(RL39-Pad6)") (class "Default")
      (node (ref "RL39") (pin "6") (pintype "passive"))
    )
    (net (code "175") (name "unconnected-(RL40-Pad4)") (class "Default")
      (node (ref "RL40") (pin "4") (pintype "passive"))
    )
    (net (code "176") (name "unconnected-(RL40-Pad5)") (class "Default")
      (node (ref "RL40") (pin "5") (pintype "passive"))
    )
    (net (code "177") (name "unconnected-(RL40-Pad6)") (class "Default")
      (node (ref "RL40") (pin "6") (pintype "passive"))
    )
    (net (code "178") (name "unconnected-(RL41-Pad4)") (class "Default")
      (node (ref "RL41") (pin "4") (pintype "passive"))
    )
    (net (code "179") (name "unconnected-(RL41-Pad5)") (class "Default")
      (node (ref "RL41") (pin "5") (pintype "passive"))
    )
    (net (code "180") (name "unconnected-(RL41-Pad6)") (class "Default")
      (node (ref "RL41") (pin "6") (pintype "passive"))
    )
    (net (code "181") (name "unconnected-(RL42-Pad4)") (class "Default")
      (node (ref "RL42") (pin "4") (pintype "passive"))
    )
    (net (code "182") (name "unconnected-(RL42-Pad5)") (class "Default")
      (node (ref "RL42") (pin "5") (pintype "passive"))
    )
    (net (code "183") (name "unconnected-(RL42-Pad6)") (class "Default")
      (node (ref "RL42") (pin "6") (pintype "passive"))
    )
    (net (code "184") (name "unconnected-(RL43-Pad4)") (class "Default")
      (node (ref "RL43") (pin "4") (pintype "passive"))
    )
    (net (code "185") (name "unconnected-(RL43-Pad5)") (class "Default")
      (node (ref "RL43") (pin "5") (pintype "passive"))
    )
    (net (code "186") (name "unconnected-(RL43-Pad6)") (class "Default")
      (node (ref "RL43") (pin "6") (pintype "passive"))
    )
    (net (code "187") (name "unconnected-(RL44-Pad4)") (class "Default")
      (node (ref "RL44") (pin "4") (pintype "passive"))
    )
    (net (code "188") (name "unconnected-(RL44-Pad5)") (class "Default")
      (node (ref "RL44") (pin "5") (pintype "passive"))
    )
    (net (code "189") (name "unconnected-(RL44-Pad6)") (class "Default")
      (node (ref "RL44") (pin "6") (pintype "passive"))
    )
    (net (code "190") (name "unconnected-(RL45-Pad4)") (class "Default")
      (node (ref "RL45") (pin "4") (pintype "passive"))
    )
    (net (code "191") (name "unconnected-(RL45-Pad5)") (class "Default")
      (node (ref "RL45") (pin "5") (pintype "passive"))
    )
    (net (code "192") (name "unconnected-(RL45-Pad6)") (class "Default")
      (node (ref "RL45") (pin "6") (pintype "passive"))
    )
    (net (code "193") (name "unconnected-(RL46-Pad4)") (class "Default")
      (node (ref "RL46") (pin "4") (pintype "passive"))
    )
    (net (code "194") (name "unconnected-(RL46-Pad5)") (class "Default")
      (node (ref "RL46") (pin "5") (pintype "passive"))
    )
    (net (code "195") (name "unconnected-(RL46-Pad6)") (class "Default")
      (node (ref "RL46") (pin "6") (pintype "passive"))
    )
    (net (code "196") (name "unconnected-(RL47-Pad4)") (class "Default")
      (node (ref "RL47") (pin "4") (pintype "passive"))
    )
    (net (code "197") (name "unconnected-(RL47-Pad5)") (class "Default")
      (node (ref "RL47") (pin "5") (pintype "passive"))
    )
    (net (code "198") (name "unconnected-(RL47-Pad6)") (class "Default")
      (node (ref "RL47") (pin "6") (pintype "passive"))
    )
    (net (code "199") (name "unconnected-(RL48-Pad4)") (class "Default")
      (node (ref "RL48") (pin "4") (pintype "passive"))
    )
    (net (code "200") (name "unconnected-(RL48-Pad5)") (class "Default")
      (node (ref "RL48") (pin "5") (pintype "passive"))
    )
    (net (code "201") (name "unconnected-(RL48-Pad6)") (class "Default")
      (node (ref "RL48") (pin "6") (pintype "passive"))
    )
    (net (code "202") (name "unconnected-(RL49-Pad4)") (class "Default")
      (node (ref "RL49") (pin "4") (pintype "passive"))
    )
    (net (code "203") (name "unconnected-(RL49-Pad5)") (class "Default")
      (node (ref "RL49") (pin "5") (pintype "passive"))
    )
    (net (code "204") (name "unconnected-(RL49-Pad6)") (class "Default")
      (node (ref "RL49") (pin "6") (pintype "passive"))
    )
    (net (code "205") (name "unconnected-(RL50-Pad4)") (class "Default")
      (node (ref "RL50") (pin "4") (pintype "passive"))
    )
    (net (code "206") (name "unconnected-(RL50-Pad5)") (class "Default")
      (node (ref "RL50") (pin "5") (pintype "passive"))
    )
    (net (code "207") (name "unconnected-(RL50-Pad6)") (class "Default")
      (node (ref "RL50") (pin "6") (pintype "passive"))
    )
    (net (code "208") (name "unconnected-(RL51-Pad4)") (class "Default")
      (node (ref "RL51") (pin "4") (pintype "passive"))
    )
    (net (code "209") (name "unconnected-(RL51-Pad5)") (class "Default")
      (node (ref "RL51") (pin "5") (pintype "passive"))
    )
    (net (code "210") (name "unconnected-(RL51-Pad6)") (class "Default")
      (node (ref "RL51") (pin "6") (pintype "passive"))
    )
    (net (code "211") (name "unconnected-(RL52-Pad4)") (class "Default")
      (node (ref "RL52") (pin "4") (pintype "passive"))
    )
    (net (code "212") (name "unconnected-(RL52-Pad5)") (class "Default")
      (node (ref "RL52") (pin "5") (pintype "passive"))
    )
    (net (code "213") (name "unconnected-(RL52-Pad6)") (class "Default")
      (node (ref "RL52") (pin "6") (pintype "passive"))
    )
    (net (code "214") (name "unconnected-(RL53-Pad4)") (class "Default")
      (node (ref "RL53") (pin "4") (pintype "passive"))
    )
    (net (code "215") (name "unconnected-(RL53-Pad5)") (class "Default")
      (node (ref "RL53") (pin "5") (pintype "passive"))
    )
    (net (code "216") (name "unconnected-(RL53-Pad6)") (class "Default")
      (node (ref "RL53") (pin "6") (pintype "passive"))
    )
    (net (code "217") (name "unconnected-(RL54-Pad4)") (class "Default")
      (node (ref "RL54") (pin "4") (pintype "passive"))
    )
    (net (code "218") (name "unconnected-(RL54-Pad5)") (class "Default")
      (node (ref "RL54") (pin "5") (pintype "passive"))
    )
    (net (code "219") (name "unconnected-(RL54-Pad6)") (class "Default")
      (node (ref "RL54") (pin "6") (pintype "passive"))
    )
    (net (code "220") (name "unconnected-(RL55-Pad4)") (class "Default")
      (node (ref "RL55") (pin "4") (pintype "passive"))
    )
    (net (code "221") (name "unconnected-(RL55-Pad5)") (class "Default")
      (node (ref "RL55") (pin "5") (pintype "passive"))
    )
    (net (code "222") (name "unconnected-(RL55-Pad6)") (class "Default")
      (node (ref "RL55") (pin "6") (pintype "passive"))
    )
    (net (code "223") (name "unconnected-(RL56-Pad4)") (class "Default")
      (node (ref "RL56") (pin "4") (pintype "passive"))
    )
    (net (code "224") (name "unconnected-(RL56-Pad5)") (class "Default")
      (node (ref "RL56") (pin "5") (pintype "passive"))
    )
    (net (code "225") (name "unconnected-(RL56-Pad6)") (class "Default")
      (node (ref "RL56") (pin "6") (pintype "passive"))
    )
    (net (code "226") (name "unconnected-(RL57-Pad4)") (class "Default")
      (node (ref "RL57") (pin "4") (pintype "passive"))
    )
    (net (code "227") (name "unconnected-(RL57-Pad5)") (class "Default")
      (node (ref "RL57") (pin "5") (pintype "passive"))
    )
    (net (code "228") (name "unconnected-(RL57-Pad6)") (class "Default")
      (node (ref "RL57") (pin "6") (pintype "passive"))
    )
    (net (code "229") (name "unconnected-(RL58-Pad4)") (class "Default")
      (node (ref "RL58") (pin "4") (pintype "passive"))
    )
    (net (code "230") (name "unconnected-(RL58-Pad5)") (class "Default")
      (node (ref "RL58") (pin "5") (pintype "passive"))
    )
    (net (code "231") (name "unconnected-(RL58-Pad6)") (class "Default")
      (node (ref "RL58") (pin "6") (pintype "passive"))
    )
    (net (code "232") (name "unconnected-(RL59-Pad4)") (class "Default")
      (node (ref "RL59") (pin "4") (pintype "passive"))
    )
    (net (code "233") (name "unconnected-(RL59-Pad5)") (class "Default")
      (node (ref "RL59") (pin "5") (pintype "passive"))
    )
    (net (code "234") (name "unconnected-(RL59-Pad6)") (class "Default")
      (node (ref "RL59") (pin "6") (pintype "passive"))
    )
    (net (code "235") (name "unconnected-(RL60-Pad4)") (class "Default")
      (node (ref "RL60") (pin "4") (pintype "passive"))
    )
    (net (code "236") (name "unconnected-(RL60-Pad5)") (class "Default")
      (node (ref "RL60") (pin "5") (pintype "passive"))
    )
    (net (code "237") (name "unconnected-(RL60-Pad6)") (class "Default")
      (node (ref "RL60") (pin "6") (pintype "passive"))
    )
    (net (code "238") (name "unconnected-(RL61-Pad4)") (class "Default")
      (node (ref "RL61") (pin "4") (pintype "passive"))
    )
    (net (code "239") (name "unconnected-(RL61-Pad5)") (class "Default")
      (node (ref "RL61") (pin "5") (pintype "passive"))
    )
    (net (code "240") (name "unconnected-(RL61-Pad6)") (class "Default")
      (node (ref "RL61") (pin "6") (pintype "passive"))
    )
    (net (code "241") (name "unconnected-(RL62-Pad4)") (class "Default")
      (node (ref "RL62") (pin "4") (pintype "passive"))
    )
    (net (code "242") (name "unconnected-(RL62-Pad5)") (class "Default")
      (node (ref "RL62") (pin "5") (pintype "passive"))
    )
    (net (code "243") (name "unconnected-(RL62-Pad6)") (class "Default")
      (node (ref "RL62") (pin "6") (pintype "passive"))
    )
    (net (code "244") (name "unconnected-(RL63-Pad4)") (class "Default")
      (node (ref "RL63") (pin "4") (pintype "passive"))
    )
    (net (code "245") (name "unconnected-(RL63-Pad5)") (class "Default")
      (node (ref "RL63") (pin "5") (pintype "passive"))
    )
    (net (code "246") (name "unconnected-(RL63-Pad6)") (class "Default")
      (node (ref "RL63") (pin "6") (pintype "passive"))
    )
    (net (code "247") (name "unconnected-(RL64-Pad4)") (class "Default")
      (node (ref "RL64") (pin "4") (pintype "passive"))
    )
    (net (code "248") (name "unconnected-(RL64-Pad5)") (class "Default")
      (node (ref "RL64") (pin "5") (pintype "passive"))
    )
    (net (code "249") (name "unconnected-(RL64-Pad6)") (class "Default")
      (node (ref "RL64") (pin "6") (pintype "passive"))
    )
    (net (code "250") (name "unconnected-(RL65-Pad4)") (class "Default")
      (node (ref "RL65") (pin "4") (pintype "passive"))
    )
    (net (code "251") (name "unconnected-(RL65-Pad5)") (class "Default")
      (node (ref "RL65") (pin "5") (pintype "passive"))
    )
    (net (code "252") (name "unconnected-(RL65-Pad6)") (class "Default")
      (node (ref "RL65") (pin "6") (pintype "passive"))
    )
    (net (code "253") (name "unconnected-(RL66-Pad4)") (class "Default")
      (node (ref "RL66") (pin "4") (pintype "passive"))
    )
    (net (code "254") (name "unconnected-(RL66-Pad5)") (class "Default")
      (node (ref "RL66") (pin "5") (pintype "passive"))
    )
    (net (code "255") (name "unconnected-(RL66-Pad6)") (class "Default")
      (node (ref "RL66") (pin "6") (pintype "passive"))
    )
    (net (code "256") (name "unconnected-(RL67-Pad4)") (class "Default")
      (node (ref "RL67") (pin "4") (pintype "passive"))
    )
    (net (code "257") (name "unconnected-(RL67-Pad5)") (class "Default")
      (node (ref "RL67") (pin "5") (pintype "passive"))
    )
    (net (code "258") (name "unconnected-(RL67-Pad6)") (class "Default")
      (node (ref "RL67") (pin "6") (pintype "passive"))
    )
    (net (code "259") (name "unconnected-(RL68-Pad4)") (class "Default")
      (node (ref "RL68") (pin "4") (pintype "passive"))
    )
    (net (code "260") (name "unconnected-(RL68-Pad5)") (class "Default")
      (node (ref "RL68") (pin "5") (pintype "passive"))
    )
    (net (code "261") (name "unconnected-(RL68-Pad6)") (class "Default")
      (node (ref "RL68") (pin "6") (pintype "passive"))
    )
    (net (code "262") (name "unconnected-(RL69-Pad4)") (class "Default")
      (node (ref "RL69") (pin "4") (pintype "passive"))
    )
    (net (code "263") (name "unconnected-(RL69-Pad5)") (class "Default")
      (node (ref "RL69") (pin "5") (pintype "passive"))
    )
    (net (code "264") (name "unconnected-(RL69-Pad6)") (class "Default")
      (node (ref "RL69") (pin "6") (pintype "passive"))
    )
    (net (code "265") (name "unconnected-(RL70-Pad4)") (class "Default")
      (node (ref "RL70") (pin "4") (pintype "passive"))
    )
    (net (code "266") (name "unconnected-(RL70-Pad5)") (class "Default")
      (node (ref "RL70") (pin "5") (pintype "passive"))
    )
    (net (code "267") (name "unconnected-(RL70-Pad6)") (class "Default")
      (node (ref "RL70") (pin "6") (pintype "passive"))
    )
    (net (code "268") (name "unconnected-(RL71-Pad4)") (class "Default")
      (node (ref "RL71") (pin "4") (pintype "passive"))
    )
    (net (code "269") (name "unconnected-(RL71-Pad5)") (class "Default")
      (node (ref "RL71") (pin "5") (pintype "passive"))
    )
    (net (code "270") (name "unconnected-(RL71-Pad6)") (class "Default")
      (node (ref "RL71") (pin "6") (pintype "passive"))
    )
    (net (code "271") (name "unconnected-(RL72-Pad4)") (class "Default")
      (node (ref "RL72") (pin "4") (pintype "passive"))
    )
    (net (code "272") (name "unconnected-(RL72-Pad5)") (class "Default")
      (node (ref "RL72") (pin "5") (pintype "passive"))
    )
    (net (code "273") (name "unconnected-(RL72-Pad6)") (class "Default")
      (node (ref "RL72") (pin "6") (pintype "passive"))
    )
  )
)
